# Sheet1.net
KiCad netlist of a schematic drawn in Altium Designer
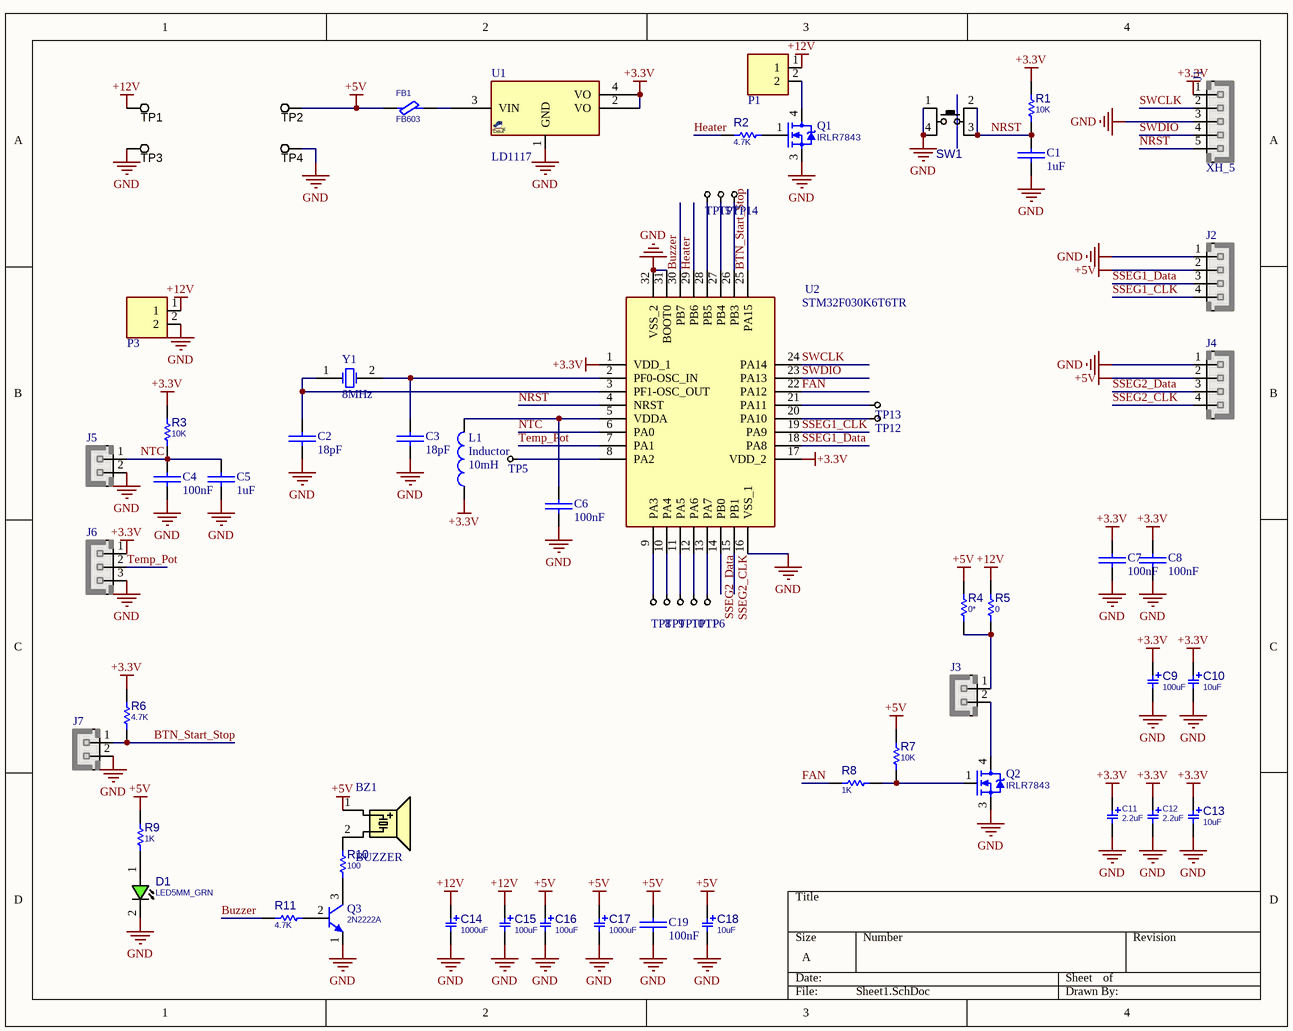
[diagram p0: Sheet1.SchDoc]

(export (version "E")
  (design (tool "Eeschema 10.0.6"))
  (components
    (comp (ref "BZ1")
      (value "BUZZER")
      (footprint "BZ_C12")
      (description "Buzzer, 12X8.5mm, Magnetic Transducer")
      (fields
        (field (name "MANF") "Buerklin, CUI")
        (field (name "MANF_P#") "CM12P, MT03-H1BHP, BMT1205XH7.5, CEM-1201(50)")
      )
      (libsource (lib "Chila Library") (part "BUZZER_C12"))
    )
    (comp (ref "C1")
      (value "1uF")
      (footprint "Cap - 100nF")
      (description "Bipolar Capacitor")
      (fields (field (name "VOLTAGE") "100V") (field (name "DESIGNER") "Saeid Jorablo"))
      (libsource (lib "My_Library") (part "Cap-Bipolar"))
    )
    (comp (ref "C2")
      (value "18pF")
      (footprint "Cap - 100nF")
      (description "Bipolar Capacitor")
      (fields (field (name "VOLTAGE") "100V") (field (name "DESIGNER") "Saeid Jorablo"))
      (libsource (lib "My_Library") (part "Cap-Bipolar"))
    )
    (comp (ref "C3")
      (value "18pF")
      (footprint "Cap - 100nF")
      (description "Bipolar Capacitor")
      (fields (field (name "VOLTAGE") "100V") (field (name "DESIGNER") "Saeid Jorablo"))
      (libsource (lib "My_Library") (part "Cap-Bipolar"))
    )
    (comp (ref "C4")
      (value "100nF")
      (footprint "Cap - 100nF")
      (description "Bipolar Capacitor")
      (fields (field (name "VOLTAGE") "100V") (field (name "DESIGNER") "Saeid Jorablo"))
      (libsource (lib "My_Library") (part "Cap-Bipolar"))
    )
    (comp (ref "C5")
      (value "1uF")
      (footprint "Cap - 100nF")
      (description "Bipolar Capacitor")
      (fields (field (name "VOLTAGE") "100V") (field (name "DESIGNER") "Saeid Jorablo"))
      (libsource (lib "My_Library") (part "Cap-Bipolar"))
    )
    (comp (ref "C6")
      (value "100nF")
      (footprint "Cap - 100nF")
      (description "Bipolar Capacitor")
      (fields (field (name "VOLTAGE") "100V") (field (name "DESIGNER") "Saeid Jorablo"))
      (libsource (lib "My_Library") (part "Cap-Bipolar"))
    )
    (comp (ref "C7")
      (value "100nF")
      (footprint "Cap - 100nF")
      (description "Bipolar Capacitor")
      (fields (field (name "VOLTAGE") "100V") (field (name "DESIGNER") "Saeid Jorablo"))
      (libsource (lib "My_Library") (part "Cap-Bipolar"))
    )
    (comp (ref "C8")
      (value "100nF")
      (footprint "Cap - 100nF")
      (description "Bipolar Capacitor")
      (fields (field (name "VOLTAGE") "100V") (field (name "DESIGNER") "Saeid Jorablo"))
      (libsource (lib "My_Library") (part "Cap-Bipolar"))
    )
    (comp (ref "C9")
      (value "100uF")
      (footprint "C_EL_6X11")
      (description "CAP, THD, ELEC,")
      (fields (field (name "MANF_P#") "MANF_PART#") (field (name "MANF") "MANF"))
      (libsource (lib "Chila Library") (part "CAP_THD_EL"))
    )
    (comp (ref "C10")
      (value "10uF")
      (footprint "C_EL_4X7")
      (description "CAP, THD, ELEC,")
      (fields (field (name "MANF_P#") "MANF_PART#") (field (name "MANF") "MANF"))
      (libsource (lib "Chila Library") (part "CAP_THD_EL_4X7"))
    )
    (comp (ref "C11")
      (value "2.2uF")
      (footprint "C_TN_3216")
      (description "CAP, SMD, TAN,")
      (libsource (lib "Chila Library") (part "CAP_SMD_TAN"))
    )
    (comp (ref "C12")
      (value "2.2uF")
      (footprint "C_TN_3216")
      (description "CAP, SMD, TAN,")
      (libsource (lib "Chila Library") (part "CAP_SMD_TAN"))
    )
    (comp (ref "C13")
      (value "10uF")
      (footprint "C_EL_4X7")
      (description "CAP, THD, ELEC,")
      (fields (field (name "MANF_P#") "MANF_PART#") (field (name "MANF") "MANF"))
      (libsource (lib "Chila Library") (part "CAP_THD_EL_4X7"))
    )
    (comp (ref "C14")
      (value "1000uF")
      (footprint "C_EL_10X12")
      (description "CAP, THD, ELEC,")
      (fields (field (name "MANF_P#") "MANF_PART#") (field (name "MANF") "MANF"))
      (libsource (lib "Chila Library") (part "CAP_THD_EL_10X12"))
    )
    (comp (ref "C15")
      (value "100uF")
      (footprint "C_EL_6X11")
      (description "CAP, THD, ELEC,")
      (fields (field (name "MANF_P#") "MANF_PART#") (field (name "MANF") "MANF"))
      (libsource (lib "Chila Library") (part "CAP_THD_EL"))
    )
    (comp (ref "C16")
      (value "100uF")
      (footprint "C_EL_6X11")
      (description "CAP, THD, ELEC,")
      (fields (field (name "MANF_P#") "MANF_PART#") (field (name "MANF") "MANF"))
      (libsource (lib "Chila Library") (part "CAP_THD_EL"))
    )
    (comp (ref "C17")
      (value "1000uF")
      (footprint "C_EL_10X12")
      (description "CAP, THD, ELEC,")
      (fields (field (name "MANF_P#") "MANF_PART#") (field (name "MANF") "MANF"))
      (libsource (lib "Chila Library") (part "CAP_THD_EL_10X12"))
    )
    (comp (ref "C18")
      (value "10uF")
      (footprint "C_EL_4X7")
      (description "CAP, THD, ELEC,")
      (fields (field (name "MANF_P#") "MANF_PART#") (field (name "MANF") "MANF"))
      (libsource (lib "Chila Library") (part "CAP_THD_EL_4X7"))
    )
    (comp (ref "C19")
      (value "100nF")
      (footprint "Cap - 100nF")
      (description "Bipolar Capacitor")
      (fields (field (name "VOLTAGE") "100V") (field (name "DESIGNER") "Saeid Jorablo"))
      (libsource (lib "My_Library") (part "Cap-Bipolar"))
    )
    (comp (ref "D1")
      (value "LED5MM_GRN")
      (footprint "LED5MM_GRN")
      (description "LED, THD, 5MM, GREEN")
      (fields (field (name "MANF") "MANF") (field (name "MANF_P#") "MANF_PART#"))
      (libsource (lib "Chila Library") (part "LED_THD_5MM_GRN"))
    )
    (comp (ref "FB1")
      (value "FB603")
      (footprint "L0805")
      (description "FERRITE_Bead, SMD")
      (fields (field (name "MANF") "MURATA") (field (name "MANF_P#") "BLM15AG121SN1D"))
      (libsource (lib "Chila Library") (part "FBEAD_SMD"))
    )
    (comp (ref "J1")
      (value "XH_5")
      (footprint "XH_5")
      (description "JST-XH pitch: 2.5mm")
      (fields (field (name "MANF_P#") "JST-B5B-XHA") (field (name "MANF") "JST"))
      (libsource (lib "Chila Library") (part "XH_5"))
    )
    (comp (ref "J2")
      (value "SSEG1")
      (footprint "XH_4")
      (description "JST-XH pitch: 2.5mm")
      (libsource (lib "Chila Library") (part "XH_4"))
    )
    (comp (ref "J3")
      (value "FAN")
      (footprint "XH_2")
      (description "JST-XH pitch: 2.5mm")
      (libsource (lib "Chila Library") (part "XH_2"))
    )
    (comp (ref "J4")
      (value "SSEG2")
      (footprint "XH_4")
      (description "JST-XH pitch: 2.5mm")
      (libsource (lib "Chila Library") (part "XH_4"))
    )
    (comp (ref "J5")
      (value "NTC")
      (footprint "XH_2")
      (description "JST-XH pitch: 2.5mm")
      (libsource (lib "Chila Library") (part "XH_2"))
    )
    (comp (ref "J6")
      (value "TEMP POT")
      (footprint "XH_3")
      (description "JST-XH pitch: 2.5mm")
      (libsource (lib "Chila Library") (part "XH_3"))
    )
    (comp (ref "J7")
      (value "BTN_Start_Stop")
      (footprint "XH_2")
      (description "JST-XH pitch: 2.5mm")
      (libsource (lib "Chila Library") (part "XH_2"))
    )
    (comp (ref "L1")
      (value "Inductor")
      (footprint "AXIAL-0.4")
      (fields (field (name "ALTIUM_VALUE") "10mH") (field (name "PUBLISHER") "Altium Limited"))
      (libsource (lib "Miscellaneous Devices") (part "Inductor"))
    )
    (comp (ref "P1")
      (value "HEATER")
      (footprint "PWL_2")
      (description "Power Terminal 2pin,Header, 2-Pin")
      (libsource (lib "Chila Library") (part "CONN_PWL_2"))
    )
    (comp (ref "P3")
      (value "POWER-IN")
      (footprint "PWL_2")
      (description "Power Terminal 2pin,Header, 2-Pin")
      (libsource (lib "Chila Library") (part "CONN_PWL_2"))
    )
    (comp (ref "Q1")
      (value "IRLR7843")
      (footprint "DPAK_3")
      (description "HEXFET Power MOSFET")
      (libsource (lib "Chila Library") (part "MOSN_IRLR7843_DPAK"))
    )
    (comp (ref "Q2")
      (value "IRLR7843")
      (footprint "DPAK_3")
      (description "HEXFET Power MOSFET")
      (libsource (lib "Chila Library") (part "MOSN_IRLR7843_DPAK"))
    )
    (comp (ref "Q3")
      (value "2N2222A")
      (footprint "TO92_3")
      (description "BJT, NPN, 40v, 0.6A, THD, TO92")
      (fields (field (name "MANF") "DIOTEC"))
      (libsource (lib "Chila Library") (part "NPN_2N2222A_TO92"))
    )
    (comp (ref "R1")
      (value "10K")
      (footprint "R025W_AX04")
      (description "RESISTOR, THD")
      (fields (field (name "MANF_P#") "RK73H1ETTP4701F") (field (name "MANF") "KOA SPEER"))
      (libsource (lib "Chila Library") (part "RES_THD"))
    )
    (comp (ref "R2")
      (value "4.7K")
      (footprint "R025W_AX04")
      (description "RESISTOR, THD")
      (fields (field (name "MANF_P#") "RK73H1ETTP4701F") (field (name "MANF") "KOA SPEER"))
      (libsource (lib "Chila Library") (part "RES_THD"))
    )
    (comp (ref "R3")
      (value "10K")
      (footprint "R025W_AX04")
      (description "RESISTOR, THD")
      (fields (field (name "MANF_P#") "RK73H1ETTP4701F") (field (name "MANF") "KOA SPEER"))
      (libsource (lib "Chila Library") (part "RES_THD"))
    )
    (comp (ref "R4")
      (value "0*")
      (footprint "R025W_AX04")
      (description "RESISTOR, THD")
      (fields (field (name "MANF_P#") "RK73H1ETTP4701F") (field (name "MANF") "KOA SPEER"))
      (libsource (lib "Chila Library") (part "RES_THD"))
    )
    (comp (ref "R5")
      (value "0")
      (footprint "R025W_AX04")
      (description "RESISTOR, THD")
      (fields (field (name "MANF_P#") "RK73H1ETTP4701F") (field (name "MANF") "KOA SPEER"))
      (libsource (lib "Chila Library") (part "RES_THD"))
    )
    (comp (ref "R6")
      (value "4.7K")
      (footprint "R025W_AX04")
      (description "RESISTOR, THD")
      (fields (field (name "MANF_P#") "RK73H1ETTP4701F") (field (name "MANF") "KOA SPEER"))
      (libsource (lib "Chila Library") (part "RES_THD"))
    )
    (comp (ref "R7")
      (value "10K")
      (footprint "R025W_AX04")
      (description "RESISTOR, THD")
      (fields (field (name "MANF_P#") "RK73H1ETTP4701F") (field (name "MANF") "KOA SPEER"))
      (libsource (lib "Chila Library") (part "RES_THD"))
    )
    (comp (ref "R8")
      (value "1K")
      (footprint "R025W_AX04")
      (description "RESISTOR, THD")
      (fields (field (name "MANF_P#") "RK73H1ETTP4701F") (field (name "MANF") "KOA SPEER"))
      (libsource (lib "Chila Library") (part "RES_THD"))
    )
    (comp (ref "R9")
      (value "1K")
      (footprint "R025W_AX04")
      (description "RESISTOR, THD")
      (fields (field (name "MANF_P#") "RK73H1ETTP4701F") (field (name "MANF") "KOA SPEER"))
      (libsource (lib "Chila Library") (part "RES_THD"))
    )
    (comp (ref "R10")
      (value "100")
      (footprint "R025W_AX04")
      (description "RESISTOR, THD")
      (fields (field (name "MANF_P#") "RK73H1ETTP4701F") (field (name "MANF") "KOA SPEER"))
      (libsource (lib "Chila Library") (part "RES_THD"))
    )
    (comp (ref "R11")
      (value "4.7K")
      (footprint "R025W_AX04")
      (description "RESISTOR, THD")
      (fields (field (name "MANF_P#") "RK73H1ETTP4701F") (field (name "MANF") "KOA SPEER"))
      (libsource (lib "Chila Library") (part "RES_THD"))
    )
    (comp (ref "SW1")
      (value "RST")
      (footprint "SWPBT_SPDT_6X6X5")
      (description "SWITCH, PUSH BUTTON, TACTILE, THD, SPDT, 4X4MM")
      (libsource (lib "Chila Library") (part "SWPBT_SPDT_6X6X5"))
    )
    (comp (ref "TP1")
      (value "IN+")
      (footprint "TP80D50")
      (description "TEST POINT")
      (fields (field (name "MANF") "MANF") (field (name "MANF_P#") "MANF_P#"))
      (libsource (lib "Chila Library") (part "TESTPOINT_PROBE"))
    )
    (comp (ref "TP2")
      (value "OUT+")
      (footprint "TP80D50")
      (description "TEST POINT")
      (fields (field (name "MANF") "MANF") (field (name "MANF_P#") "MANF_P#"))
      (libsource (lib "Chila Library") (part "TESTPOINT_PROBE"))
    )
    (comp (ref "TP3")
      (value "IN-")
      (footprint "TP80D50")
      (description "TEST POINT")
      (fields (field (name "MANF") "MANF") (field (name "MANF_P#") "MANF_P#"))
      (libsource (lib "Chila Library") (part "TESTPOINT_PROBE"))
    )
    (comp (ref "TP4")
      (value "OUT-")
      (footprint "TP80D50")
      (description "TEST POINT")
      (fields (field (name "MANF") "MANF") (field (name "MANF_P#") "MANF_P#"))
      (libsource (lib "Chila Library") (part "TESTPOINT_PROBE"))
    )
    (comp (ref "TP5")
      (value "~")
      (footprint "TP10")
      (description "Test Point")
      (fields (field (name "DESIGNER") "Eng. Saeid Jorablo"))
      (libsource (lib "SJ Passive Components") (part "Test Point"))
    )
    (comp (ref "TP6")
      (value "~")
      (footprint "TP10")
      (description "Test Point")
      (fields (field (name "DESIGNER") "Eng. Saeid Jorablo"))
      (libsource (lib "SJ Passive Components") (part "Test Point"))
    )
    (comp (ref "TP7")
      (value "~")
      (footprint "TP10")
      (description "Test Point")
      (fields (field (name "DESIGNER") "Eng. Saeid Jorablo"))
      (libsource (lib "SJ Passive Components") (part "Test Point"))
    )
    (comp (ref "TP8")
      (value "~")
      (footprint "TP10")
      (description "Test Point")
      (fields (field (name "DESIGNER") "Eng. Saeid Jorablo"))
      (libsource (lib "SJ Passive Components") (part "Test Point"))
    )
    (comp (ref "TP9")
      (value "~")
      (footprint "TP10")
      (description "Test Point")
      (fields (field (name "DESIGNER") "Eng. Saeid Jorablo"))
      (libsource (lib "SJ Passive Components") (part "Test Point"))
    )
    (comp (ref "TP10")
      (value "~")
      (footprint "TP10")
      (description "Test Point")
      (fields (field (name "DESIGNER") "Eng. Saeid Jorablo"))
      (libsource (lib "SJ Passive Components") (part "Test Point"))
    )
    (comp (ref "TP11")
      (value "~")
      (footprint "TP10")
      (description "Test Point")
      (fields (field (name "DESIGNER") "Eng. Saeid Jorablo"))
      (libsource (lib "SJ Passive Components") (part "Test Point"))
    )
    (comp (ref "TP12")
      (value "~")
      (footprint "TP10")
      (description "Test Point")
      (fields (field (name "DESIGNER") "Eng. Saeid Jorablo"))
      (libsource (lib "SJ Passive Components") (part "Test Point"))
    )
    (comp (ref "TP13")
      (value "~")
      (footprint "TP10")
      (description "Test Point")
      (fields (field (name "DESIGNER") "Eng. Saeid Jorablo"))
      (libsource (lib "SJ Passive Components") (part "Test Point"))
    )
    (comp (ref "TP14")
      (value "~")
      (footprint "TP10")
      (description "Test Point")
      (fields (field (name "DESIGNER") "Eng. Saeid Jorablo"))
      (libsource (lib "SJ Passive Components") (part "Test Point"))
    )
    (comp (ref "TP15")
      (value "~")
      (footprint "TP10")
      (description "Test Point")
      (fields (field (name "DESIGNER") "Eng. Saeid Jorablo"))
      (libsource (lib "SJ Passive Components") (part "Test Point"))
    )
    (comp (ref "U1")
      (value "LD1117")
      (footprint "SOT223_4")
      (description "REG, Linear, LDO1V, 0.8A, SOT-223")
      (fields
        (field (name "MANF_P#") "LD1117, LM1117, AMS1117, TLV1117, REG1117, NCP1117, LT1117, SPX1117")
        (field (name "MANF") "TI, ON, ST")
      )
      (libsource (lib "Chila Library") (part "VREG_1117_SOT223"))
    )
    (comp (ref "U2")
      (value "STM32F030K6T6TR")
      (footprint "SamacSys:QFP80P900X900X160-32N")
      (description "Integrated Circuit")
      (fields (field (name "MOUSER PART NUMBER") "511-STM32F030K6T6TR"))
      (libsource (lib "SamacSys") (part "STM32F030K6T6TR"))
    )
    (comp (ref "Y1")
      (value "8MHz")
      (footprint "XTAL Small")
      (description "XTAL Crystal")
      (libsource (lib "My_Library") (part "XTAL"))
    )
  )
  (nets
    (net (code "1") (name "+3.3V") (class "Default")
      (node (ref "C10") (pin "1") (pinfunction "1_1") (pintype "passive"))
      (node (ref "C11") (pin "1") (pinfunction "1_1") (pintype "passive"))
      (node (ref "C12") (pin "1") (pinfunction "1_1") (pintype "passive"))
      (node (ref "C13") (pin "1") (pinfunction "1_1") (pintype "passive"))
      (node (ref "C7") (pin "1") (pinfunction "+_1") (pintype "passive"))
      (node (ref "C8") (pin "1") (pinfunction "+_1") (pintype "passive"))
      (node (ref "C9") (pin "1") (pinfunction "1_1") (pintype "passive"))
      (node (ref "J1") (pin "1") (pinfunction "1_1") (pintype "passive"))
      (node (ref "J6") (pin "1") (pinfunction "1_1") (pintype "passive"))
      (node (ref "L1") (pin "1") (pinfunction "1_1") (pintype "passive"))
      (node (ref "R1") (pin "2") (pinfunction "2_2") (pintype "passive"))
      (node (ref "R3") (pin "2") (pinfunction "2_2") (pintype "passive"))
      (node (ref "R6") (pin "2") (pinfunction "2_2") (pintype "passive"))
      (node (ref "U1") (pin "2") (pinfunction "VO_2") (pintype "passive"))
      (node (ref "U1") (pin "4") (pinfunction "VO_4") (pintype "passive"))
      (node (ref "U2") (pin "1") (pinfunction "VDD_1_1") (pintype "passive"))
      (node (ref "U2") (pin "17") (pinfunction "VDD_2_17") (pintype "passive"))
    )
    (net (code "2") (name "+5V") (class "Default")
      (node (ref "BZ1") (pin "1") (pinfunction "A_1") (pintype "passive"))
      (node (ref "C16") (pin "1") (pinfunction "1_1") (pintype "passive"))
      (node (ref "C17") (pin "1") (pinfunction "1_1") (pintype "passive"))
      (node (ref "C18") (pin "1") (pinfunction "1_1") (pintype "passive"))
      (node (ref "C19") (pin "1") (pinfunction "+_1") (pintype "passive"))
      (node (ref "FB1") (pin "1") (pinfunction "1_1") (pintype "passive"))
      (node (ref "J2") (pin "2") (pinfunction "2_2") (pintype "passive"))
      (node (ref "J4") (pin "2") (pinfunction "2_2") (pintype "passive"))
      (node (ref "R4") (pin "2") (pinfunction "2_2") (pintype "passive"))
      (node (ref "R7") (pin "2") (pinfunction "2_2") (pintype "passive"))
      (node (ref "R9") (pin "2") (pinfunction "2_2") (pintype "passive"))
      (node (ref "TP2") (pin "1") (pinfunction "1_1") (pintype "passive"))
    )
    (net (code "3") (name "+12V") (class "Default")
      (node (ref "C14") (pin "1") (pinfunction "1_1") (pintype "passive"))
      (node (ref "C15") (pin "1") (pinfunction "1_1") (pintype "passive"))
      (node (ref "P1") (pin "1") (pinfunction "1_1") (pintype "passive"))
      (node (ref "P3") (pin "1") (pinfunction "1_1") (pintype "passive"))
      (node (ref "R5") (pin "2") (pinfunction "2_2") (pintype "passive"))
      (node (ref "TP1") (pin "1") (pinfunction "1_1") (pintype "passive"))
    )
    (net (code "4") (name "/BTN_Start_Stop") (class "Default")
      (node (ref "J7") (pin "1") (pinfunction "1_1") (pintype "passive"))
      (node (ref "R6") (pin "1") (pinfunction "1_1") (pintype "passive"))
      (node (ref "U2") (pin "25") (pinfunction "PA15_25") (pintype "passive"))
    )
    (net (code "5") (name "/Buzzer") (class "Default")
      (node (ref "R11") (pin "2") (pinfunction "2_2") (pintype "passive"))
      (node (ref "U2") (pin "30") (pinfunction "PB7_30") (pintype "passive"))
    )
    (net (code "6") (name "/FAN") (class "Default")
      (node (ref "R8") (pin "1") (pinfunction "1_1") (pintype "passive"))
      (node (ref "U2") (pin "22") (pinfunction "PA12_22") (pintype "passive"))
    )
    (net (code "7") (name "/Heater") (class "Default")
      (node (ref "R2") (pin "1") (pinfunction "1_1") (pintype "passive"))
      (node (ref "U2") (pin "29") (pinfunction "PB6_29") (pintype "passive"))
    )
    (net (code "8") (name "/NRST") (class "Default")
      (node (ref "C1") (pin "1") (pinfunction "+_1") (pintype "passive"))
      (node (ref "J1") (pin "5") (pinfunction "5_5") (pintype "passive"))
      (node (ref "R1") (pin "1") (pinfunction "1_1") (pintype "passive"))
      (node (ref "SW1") (pin "2") (pinfunction "P3_2") (pintype "passive"))
      (node (ref "SW1") (pin "3") (pinfunction "P4_3") (pintype "passive"))
      (node (ref "U2") (pin "4") (pinfunction "NRST_4") (pintype "passive"))
    )
    (net (code "9") (name "/NTC") (class "Default")
      (node (ref "C4") (pin "1") (pinfunction "+_1") (pintype "passive"))
      (node (ref "C5") (pin "1") (pinfunction "+_1") (pintype "passive"))
      (node (ref "J5") (pin "1") (pinfunction "1_1") (pintype "passive"))
      (node (ref "R3") (pin "1") (pinfunction "1_1") (pintype "passive"))
      (node (ref "U2") (pin "6") (pinfunction "PA0_6") (pintype "passive"))
    )
    (net (code "10") (name "/SSEG1_CLK") (class "Default")
      (node (ref "J2") (pin "4") (pinfunction "4_4") (pintype "passive"))
      (node (ref "U2") (pin "19") (pinfunction "PA9_19") (pintype "passive"))
    )
    (net (code "11") (name "/SSEG1_Data") (class "Default")
      (node (ref "J2") (pin "3") (pinfunction "3_3") (pintype "passive"))
      (node (ref "U2") (pin "18") (pinfunction "PA8_18") (pintype "passive"))
    )
    (net (code "12") (name "/SSEG2_CLK") (class "Default")
      (node (ref "J4") (pin "4") (pinfunction "4_4") (pintype "passive"))
      (node (ref "U2") (pin "15") (pinfunction "PB1_15") (pintype "passive"))
    )
    (net (code "13") (name "/SSEG2_Data") (class "Default")
      (node (ref "J4") (pin "3") (pinfunction "3_3") (pintype "passive"))
      (node (ref "U2") (pin "14") (pinfunction "PB0_14") (pintype "passive"))
    )
    (net (code "14") (name "/SWCLK") (class "Default")
      (node (ref "J1") (pin "2") (pinfunction "2_2") (pintype "passive"))
      (node (ref "U2") (pin "24") (pinfunction "PA14_24") (pintype "passive"))
    )
    (net (code "15") (name "/SWDIO") (class "Default")
      (node (ref "J1") (pin "4") (pinfunction "4_4") (pintype "passive"))
      (node (ref "U2") (pin "23") (pinfunction "PA13_23") (pintype "passive"))
    )
    (net (code "16") (name "/Temp_Pot") (class "Default")
      (node (ref "J6") (pin "2") (pinfunction "2_2") (pintype "passive"))
      (node (ref "U2") (pin "7") (pinfunction "PA1_7") (pintype "passive"))
    )
    (net (code "17") (name "GND") (class "Default")
      (node (ref "C1") (pin "2") (pinfunction "-_2") (pintype "passive"))
      (node (ref "C10") (pin "2") (pinfunction "2_2") (pintype "passive"))
      (node (ref "C11") (pin "2") (pinfunction "2_2") (pintype "passive"))
      (node (ref "C12") (pin "2") (pinfunction "2_2") (pintype "passive"))
      (node (ref "C13") (pin "2") (pinfunction "2_2") (pintype "passive"))
      (node (ref "C14") (pin "2") (pinfunction "2_2") (pintype "passive"))
      (node (ref "C15") (pin "2") (pinfunction "2_2") (pintype "passive"))
      (node (ref "C16") (pin "2") (pinfunction "2_2") (pintype "passive"))
      (node (ref "C17") (pin "2") (pinfunction "2_2") (pintype "passive"))
      (node (ref "C18") (pin "2") (pinfunction "2_2") (pintype "passive"))
      (node (ref "C19") (pin "2") (pinfunction "-_2") (pintype "passive"))
      (node (ref "C2") (pin "2") (pinfunction "-_2") (pintype "passive"))
      (node (ref "C3") (pin "2") (pinfunction "-_2") (pintype "passive"))
      (node (ref "C4") (pin "2") (pinfunction "-_2") (pintype "passive"))
      (node (ref "C5") (pin "2") (pinfunction "-_2") (pintype "passive"))
      (node (ref "C6") (pin "2") (pinfunction "-_2") (pintype "passive"))
      (node (ref "C7") (pin "2") (pinfunction "-_2") (pintype "passive"))
      (node (ref "C8") (pin "2") (pinfunction "-_2") (pintype "passive"))
      (node (ref "C9") (pin "2") (pinfunction "2_2") (pintype "passive"))
      (node (ref "D1") (pin "2") (pinfunction "CATHODE_2") (pintype "passive"))
      (node (ref "J1") (pin "3") (pinfunction "3_3") (pintype "passive"))
      (node (ref "J2") (pin "1") (pinfunction "1_1") (pintype "passive"))
      (node (ref "J4") (pin "1") (pinfunction "1_1") (pintype "passive"))
      (node (ref "J5") (pin "2") (pinfunction "2_2") (pintype "passive"))
      (node (ref "J6") (pin "3") (pinfunction "3_3") (pintype "passive"))
      (node (ref "J7") (pin "2") (pinfunction "2_2") (pintype "passive"))
      (node (ref "P3") (pin "2") (pinfunction "2_2") (pintype "passive"))
      (node (ref "Q1") (pin "3") (pinfunction "S_3") (pintype "passive"))
      (node (ref "Q2") (pin "3") (pinfunction "S_3") (pintype "passive"))
      (node (ref "Q3") (pin "1") (pinfunction "E_1") (pintype "passive"))
      (node (ref "SW1") (pin "1") (pinfunction "P1_1") (pintype "passive"))
      (node (ref "SW1") (pin "4") (pinfunction "P2_4") (pintype "passive"))
      (node (ref "TP3") (pin "1") (pinfunction "1_1") (pintype "passive"))
      (node (ref "TP4") (pin "1") (pinfunction "1_1") (pintype "passive"))
      (node (ref "U1") (pin "1") (pinfunction "GND_1") (pintype "passive"))
      (node (ref "U2") (pin "16") (pinfunction "VSS_1_16") (pintype "passive"))
      (node (ref "U2") (pin "31") (pinfunction "BOOT0_31") (pintype "passive"))
      (node (ref "U2") (pin "32") (pinfunction "VSS_2_32") (pintype "passive"))
    )
    (net (code "18") (name "Net-(BZ1-B)") (class "Default")
      (node (ref "BZ1") (pin "2") (pinfunction "B_2") (pintype "passive"))
      (node (ref "R10") (pin "2") (pinfunction "2_2") (pintype "passive"))
    )
    (net (code "19") (name "Net-(C2-+)") (class "Default")
      (node (ref "C2") (pin "1") (pinfunction "+_1") (pintype "passive"))
      (node (ref "U2") (pin "3") (pinfunction "PF1-OSC_OUT_3") (pintype "passive"))
      (node (ref "Y1") (pin "1") (pinfunction "OSC1_1") (pintype "passive"))
    )
    (net (code "20") (name "Net-(C3-+)") (class "Default")
      (node (ref "C3") (pin "1") (pinfunction "+_1") (pintype "passive"))
      (node (ref "U2") (pin "2") (pinfunction "PF0-OSC_IN_2") (pintype "passive"))
      (node (ref "Y1") (pin "2") (pinfunction "OSC2_2") (pintype "passive"))
    )
    (net (code "21") (name "Net-(C6-+)") (class "Default")
      (node (ref "C6") (pin "1") (pinfunction "+_1") (pintype "passive"))
      (node (ref "L1") (pin "2") (pinfunction "2_2") (pintype "passive"))
      (node (ref "U2") (pin "5") (pinfunction "VDDA_5") (pintype "passive"))
    )
    (net (code "22") (name "Net-(D1-ANODE)") (class "Default")
      (node (ref "D1") (pin "1") (pinfunction "ANODE_1") (pintype "passive"))
      (node (ref "R9") (pin "1") (pinfunction "1_1") (pintype "passive"))
    )
    (net (code "23") (name "Net-(J3-Pad1)") (class "Default")
      (node (ref "J3") (pin "1") (pinfunction "1_1") (pintype "passive"))
      (node (ref "R4") (pin "1") (pinfunction "1_1") (pintype "passive"))
      (node (ref "R5") (pin "1") (pinfunction "1_1") (pintype "passive"))
    )
    (net (code "24") (name "Net-(Q1-D)") (class "Default")
      (node (ref "P1") (pin "2") (pinfunction "2_2") (pintype "passive"))
      (node (ref "Q1") (pin "4") (pinfunction "D_4") (pintype "passive"))
    )
    (net (code "25") (name "Net-(Q1-G)") (class "Default")
      (node (ref "Q1") (pin "1") (pinfunction "G_1") (pintype "passive"))
      (node (ref "R2") (pin "2") (pinfunction "2_2") (pintype "passive"))
    )
    (net (code "26") (name "Net-(Q2-D)") (class "Default")
      (node (ref "J3") (pin "2") (pinfunction "2_2") (pintype "passive"))
      (node (ref "Q2") (pin "4") (pinfunction "D_4") (pintype "passive"))
    )
    (net (code "27") (name "Net-(Q2-G)") (class "Default")
      (node (ref "Q2") (pin "1") (pinfunction "G_1") (pintype "passive"))
      (node (ref "R7") (pin "1") (pinfunction "1_1") (pintype "passive"))
      (node (ref "R8") (pin "2") (pinfunction "2_2") (pintype "passive"))
    )
    (net (code "28") (name "Net-(Q3-B)") (class "Default")
      (node (ref "Q3") (pin "2") (pinfunction "B_2") (pintype "passive"))
      (node (ref "R11") (pin "1") (pinfunction "1_1") (pintype "passive"))
    )
    (net (code "29") (name "Net-(Q3-C)") (class "Default")
      (node (ref "Q3") (pin "3") (pinfunction "C_3") (pintype "passive"))
      (node (ref "R10") (pin "1") (pinfunction "1_1") (pintype "passive"))
    )
    (net (code "30") (name "Net-(TP5-TP)") (class "Default")
      (node (ref "TP5") (pin "1") (pinfunction "TP_1") (pintype "passive"))
      (node (ref "U2") (pin "8") (pinfunction "PA2_8") (pintype "passive"))
    )
    (net (code "31") (name "Net-(TP6-TP)") (class "Default")
      (node (ref "TP6") (pin "1") (pinfunction "TP_1") (pintype "passive"))
      (node (ref "U2") (pin "13") (pinfunction "PA7_13") (pintype "passive"))
    )
    (net (code "32") (name "Net-(TP7-TP)") (class "Default")
      (node (ref "TP7") (pin "1") (pinfunction "TP_1") (pintype "passive"))
      (node (ref "U2") (pin "27") (pinfunction "PB4_27") (pintype "passive"))
    )
    (net (code "33") (name "Net-(TP8-TP)") (class "Default")
      (node (ref "TP8") (pin "1") (pinfunction "TP_1") (pintype "passive"))
      (node (ref "U2") (pin "9") (pinfunction "PA3_9") (pintype "passive"))
    )
    (net (code "34") (name "Net-(TP9-TP)") (class "Default")
      (node (ref "TP9") (pin "1") (pinfunction "TP_1") (pintype "passive"))
      (node (ref "U2") (pin "10") (pinfunction "PA4_10") (pintype "passive"))
    )
    (net (code "35") (name "Net-(TP10-TP)") (class "Default")
      (node (ref "TP10") (pin "1") (pinfunction "TP_1") (pintype "passive"))
      (node (ref "U2") (pin "11") (pinfunction "PA5_11") (pintype "passive"))
    )
    (net (code "36") (name "Net-(TP11-TP)") (class "Default")
      (node (ref "TP11") (pin "1") (pinfunction "TP_1") (pintype "passive"))
      (node (ref "U2") (pin "12") (pinfunction "PA6_12") (pintype "passive"))
    )
    (net (code "37") (name "Net-(TP12-TP)") (class "Default")
      (node (ref "TP12") (pin "1") (pinfunction "TP_1") (pintype "passive"))
      (node (ref "U2") (pin "20") (pinfunction "PA10_20") (pintype "passive"))
    )
    (net (code "38") (name "Net-(TP13-TP)") (class "Default")
      (node (ref "TP13") (pin "1") (pinfunction "TP_1") (pintype "passive"))
      (node (ref "U2") (pin "21") (pinfunction "PA11_21") (pintype "passive"))
    )
    (net (code "39") (name "Net-(TP14-TP)") (class "Default")
      (node (ref "TP14") (pin "1") (pinfunction "TP_1") (pintype "passive"))
      (node (ref "U2") (pin "26") (pinfunction "PB3_26") (pintype "passive"))
    )
    (net (code "40") (name "Net-(TP15-TP)") (class "Default")
      (node (ref "TP15") (pin "1") (pinfunction "TP_1") (pintype "passive"))
      (node (ref "U2") (pin "28") (pinfunction "PB5_28") (pintype "passive"))
    )
    (net (code "41") (name "Net-(U1-VIN)") (class "Default")
      (node (ref "FB1") (pin "2") (pinfunction "2_2") (pintype "passive"))
      (node (ref "U1") (pin "3") (pinfunction "VIN_3") (pintype "passive"))
    )
  )
)
